# 02_-_BOOT-Select.net
KiCad netlist of a schematic drawn in Altium Designer
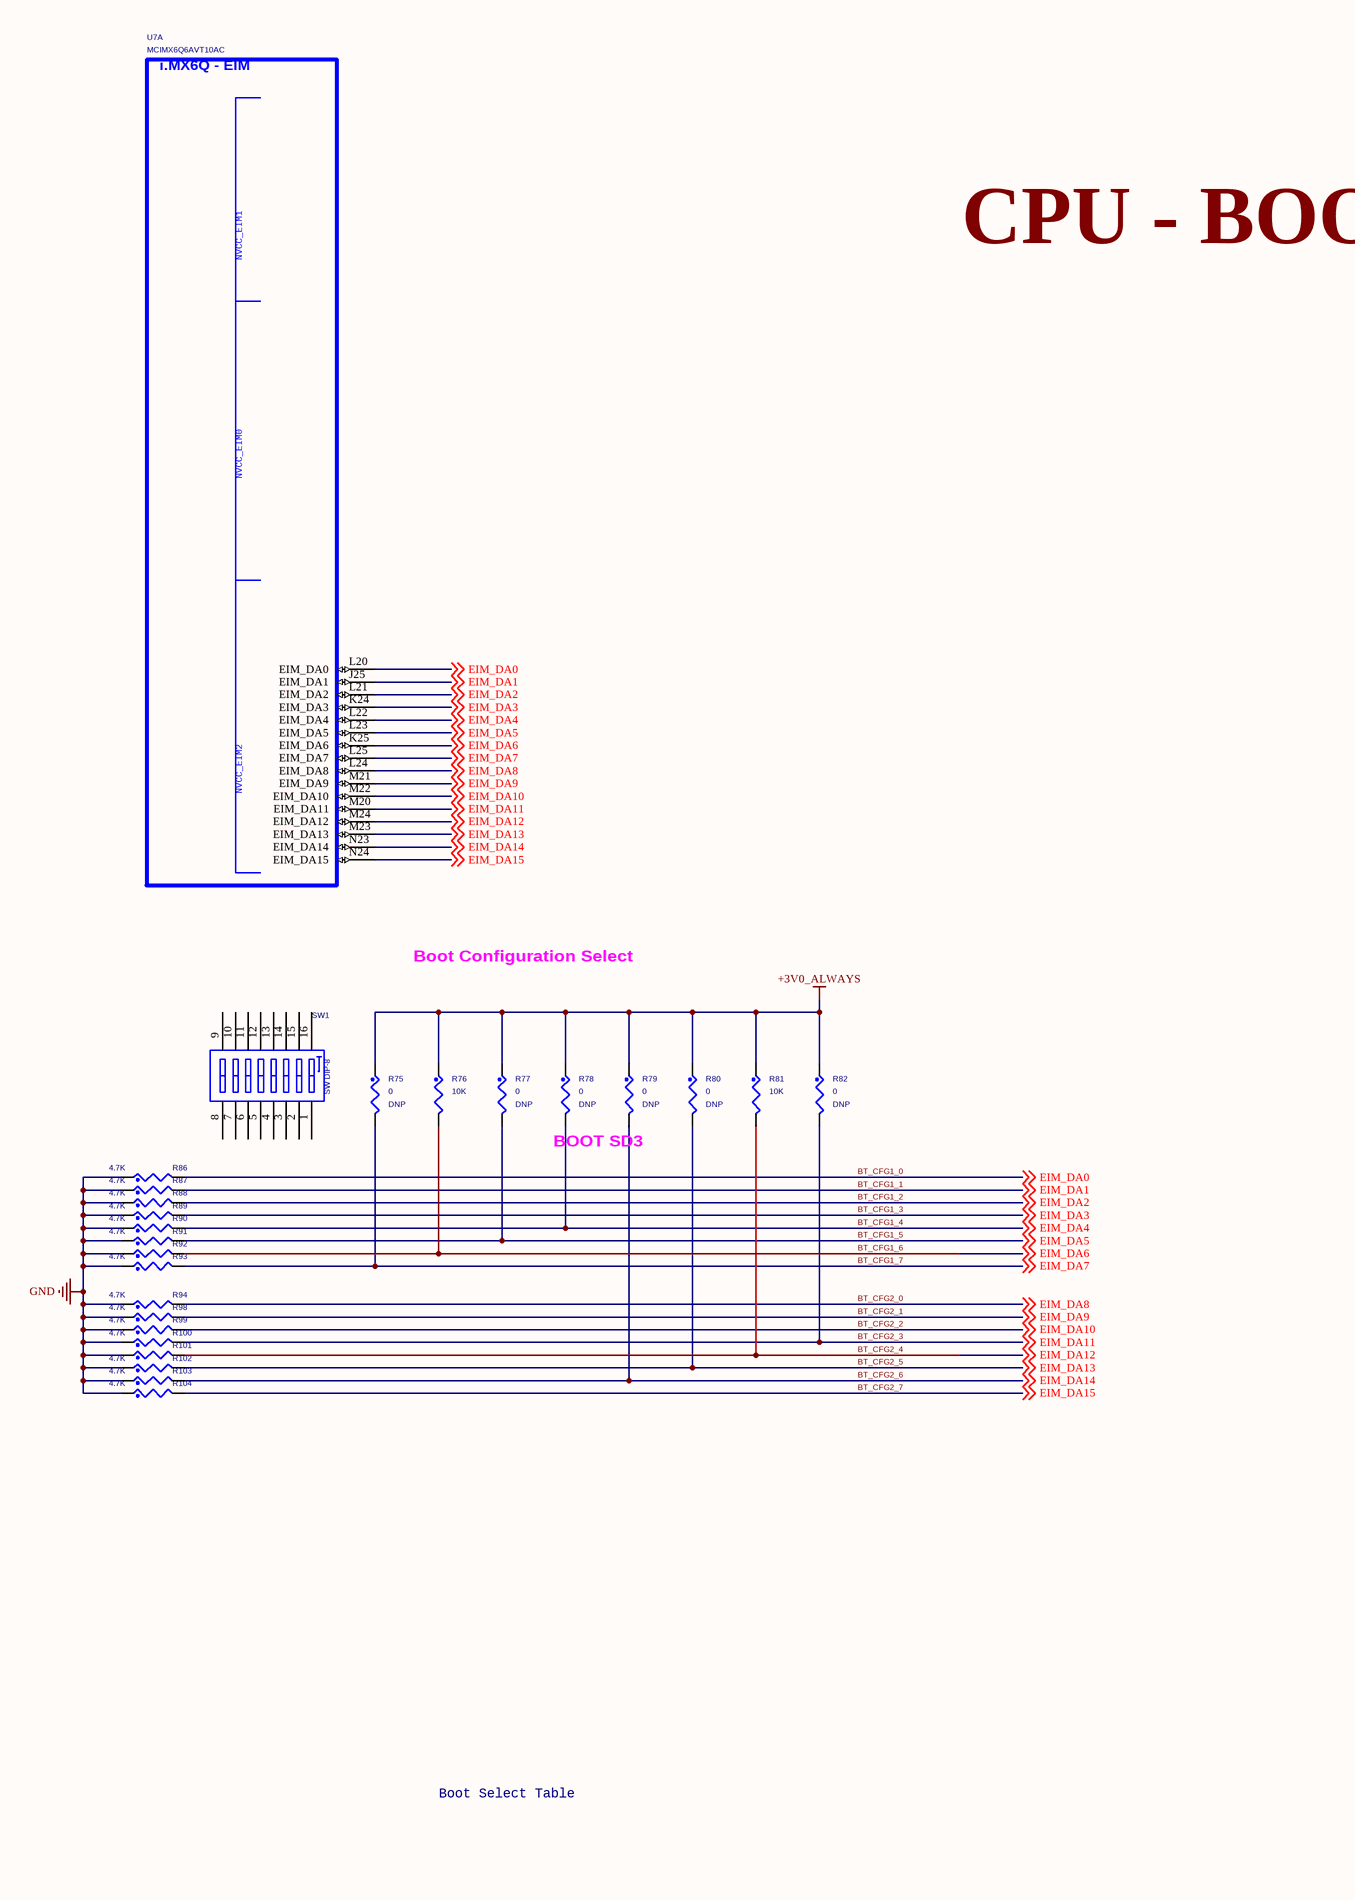
[diagram p0: [02] - BOOT-Select.SchDoc, left]
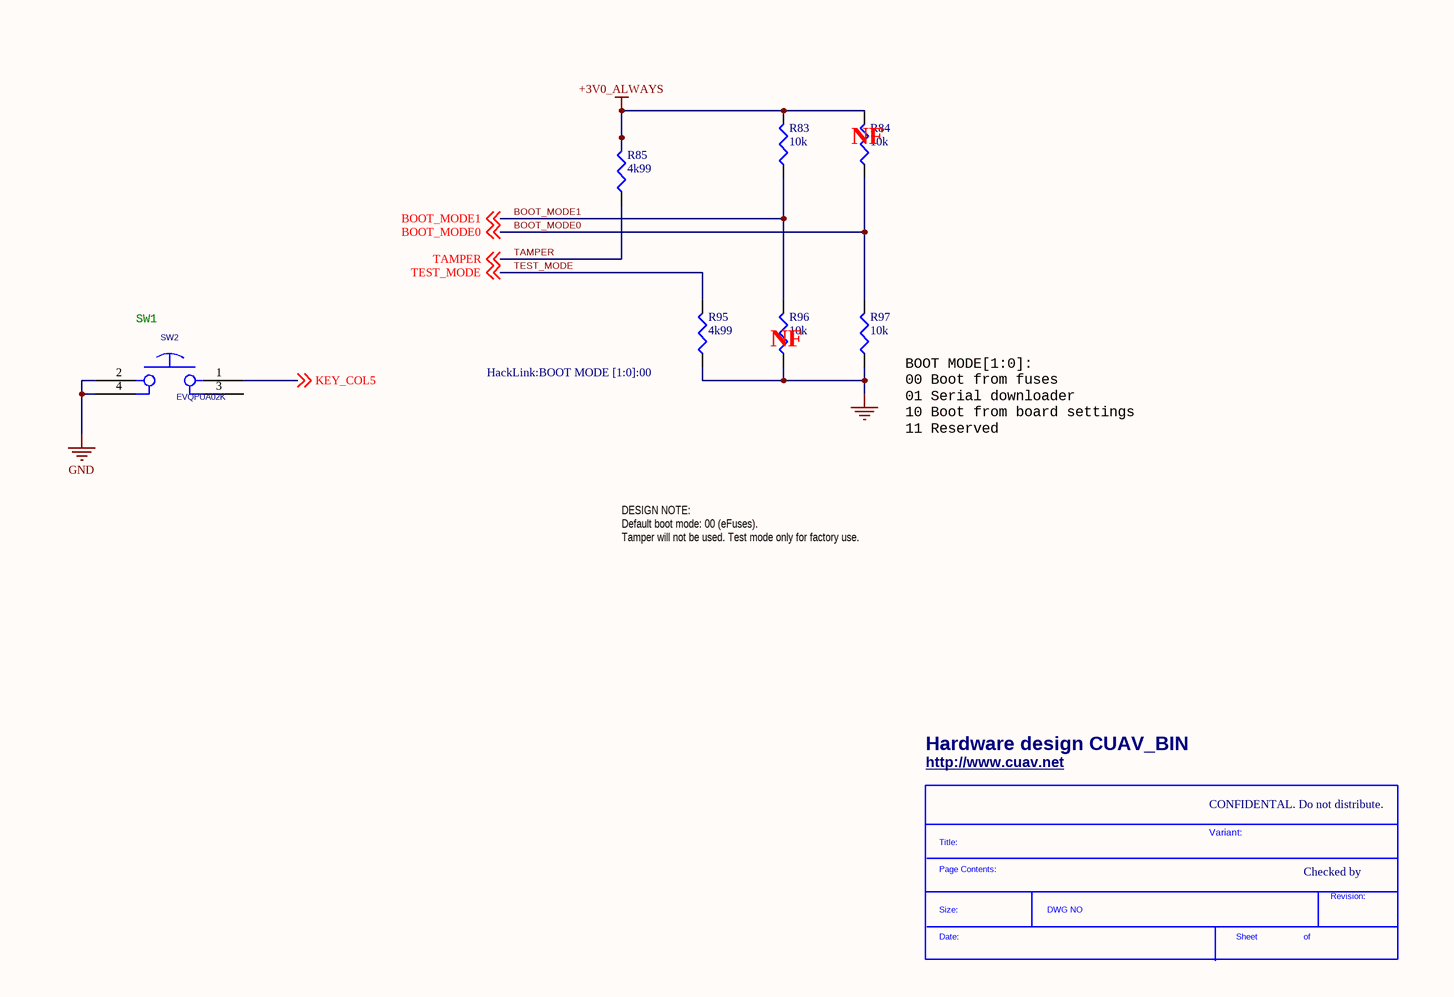
[diagram p1: [02] - BOOT-Select.SchDoc, right]

(export (version "E")
  (design (tool "Eeschema 10.0.6"))
  (components
    (comp (ref "*") (value "SDTitleBlock") (libsource (lib "*") (part "SDTitleBlock")))
    (comp (ref "R75")
      (value "0")
      (description "RES MF ZERO OHM 1/10W -- 0402")
      (fields (field (name "ASSY_OPT") "DNP"))
      (libsource (lib "*") (part "RES"))
    )
    (comp (ref "R76")
      (value "10K")
      (description "RES MF ZERO OHM 1/10W -- 0402")
      (libsource (lib "*") (part "RES"))
    )
    (comp (ref "R77")
      (value "0")
      (description "RES MF ZERO OHM 1/10W -- 0402")
      (fields (field (name "ASSY_OPT") "DNP"))
      (libsource (lib "*") (part "RES"))
    )
    (comp (ref "R78")
      (value "0")
      (description "RES MF ZERO OHM 1/10W -- 0402")
      (fields (field (name "ASSY_OPT") "DNP"))
      (libsource (lib "*") (part "RES"))
    )
    (comp (ref "R79")
      (value "0")
      (description "RES MF ZERO OHM 1/10W -- 0402")
      (fields (field (name "ASSY_OPT") "DNP"))
      (libsource (lib "*") (part "RES"))
    )
    (comp (ref "R80")
      (value "0")
      (description "RES MF ZERO OHM 1/10W -- 0402")
      (fields (field (name "ASSY_OPT") "DNP"))
      (libsource (lib "*") (part "RES"))
    )
    (comp (ref "R81")
      (value "10K")
      (description "RES MF ZERO OHM 1/10W -- 0402")
      (libsource (lib "*") (part "RES"))
    )
    (comp (ref "R82")
      (value "0")
      (description "RES MF ZERO OHM 1/10W -- 0402")
      (fields (field (name "ASSY_OPT") "DNP"))
      (libsource (lib "*") (part "RES"))
    )
    (comp (ref "R83")
      (value "10k")
      (footprint "R0402")
      (description "RES 10.0K OHM 1/16W 1% 0402 SMD")
      (fields
        (field (name "MANUFACTURER") "Yageo")
        (field (name "MANUFACTURER PART NUMBER") "RC0402FR-0710KL")
      )
      (libsource (lib "Integrated_Library_RF_FEB_2012") (part "RC0402FR-0710KL"))
    )
    (comp (ref "R84")
      (value "10k")
      (footprint "R0402")
      (description "RES 10.0K OHM 1/16W 1% 0402 SMD")
      (fields
        (field (name "MANUFACTURER") "Yageo")
        (field (name "MANUFACTURER PART NUMBER") "RC0402FR-0710KL")
      )
      (libsource (lib "Integrated_Library_RF_FEB_2012") (part "RC0402FR-0710KL"))
    )
    (comp (ref "R85")
      (value "4k99")
      (footprint "R0402")
      (description "RES TF 4.99K OHM 1% 1/16W 0402")
      (fields
        (field (name "MANUFACTURER") "Stackpole Electronics Inc")
        (field (name "MANUFACTURER PART NUMBER") "RMCF0402FT4K99")
      )
      (libsource (lib "Integrated_Library_RF_FEB_2012") (part "RMCF0402FT4K99"))
    )
    (comp (ref "R86")
      (value "4.7K")
      (description "RES MF 4.70K 1/16W 1% 0402")
      (fields (field (name "TOLERANCE") "1%"))
      (libsource (lib "*") (part "RES"))
    )
    (comp (ref "R87")
      (value "4.7K")
      (description "RES MF 4.70K 1/16W 1% 0402")
      (fields (field (name "TOLERANCE") "1%"))
      (libsource (lib "*") (part "RES"))
    )
    (comp (ref "R88")
      (value "4.7K")
      (description "RES MF 4.70K 1/16W 1% 0402")
      (fields (field (name "TOLERANCE") "1%"))
      (libsource (lib "*") (part "RES"))
    )
    (comp (ref "R89")
      (value "4.7K")
      (description "RES MF 4.70K 1/16W 1% 0402")
      (fields (field (name "TOLERANCE") "1%"))
      (libsource (lib "*") (part "RES"))
    )
    (comp (ref "R90")
      (value "4.7K")
      (description "RES MF 4.70K 1/16W 1% 0402")
      (fields (field (name "TOLERANCE") "1%"))
      (libsource (lib "*") (part "RES"))
    )
    (comp (ref "R91")
      (value "4.7K")
      (description "RES MF 4.70K 1/16W 1% 0402")
      (fields (field (name "TOLERANCE") "1%"))
      (libsource (lib "*") (part "RES"))
    )
    (comp (ref "R92")
      (value "~")
      (description "RES MF 4.70K 1/16W 1% 0402")
      (fields (field (name "TOLERANCE") "1%"))
      (libsource (lib "*") (part "RES"))
    )
    (comp (ref "R93")
      (value "4.7K")
      (description "RES MF 4.70K 1/16W 1% 0402")
      (fields (field (name "TOLERANCE") "1%"))
      (libsource (lib "*") (part "RES"))
    )
    (comp (ref "R94")
      (value "4.7K")
      (description "RES MF 4.70K 1/16W 1% 0402")
      (fields (field (name "TOLERANCE") "1%"))
      (libsource (lib "*") (part "RES"))
    )
    (comp (ref "R95")
      (value "4k99")
      (footprint "R0402")
      (description "RES TF 4.99K OHM 1% 1/16W 0402")
      (fields
        (field (name "MANUFACTURER") "Stackpole Electronics Inc")
        (field (name "MANUFACTURER PART NUMBER") "RMCF0402FT4K99")
      )
      (libsource (lib "Integrated_Library_RF_FEB_2012") (part "RMCF0402FT4K99"))
    )
    (comp (ref "R96")
      (value "10k")
      (footprint "R0402")
      (description "RES 10.0K OHM 1/16W 1% 0402 SMD")
      (fields
        (field (name "MANUFACTURER") "Yageo")
        (field (name "MANUFACTURER PART NUMBER") "RC0402FR-0710KL")
      )
      (libsource (lib "Integrated_Library_RF_FEB_2012") (part "RC0402FR-0710KL"))
    )
    (comp (ref "R97")
      (value "10k")
      (footprint "R0402")
      (description "RES 10.0K OHM 1/16W 1% 0402 SMD")
      (fields
        (field (name "MANUFACTURER") "Yageo")
        (field (name "MANUFACTURER PART NUMBER") "RC0402FR-0710KL")
      )
      (libsource (lib "Integrated_Library_RF_FEB_2012") (part "RC0402FR-0710KL"))
    )
    (comp (ref "R98")
      (value "4.7K")
      (description "RES MF 4.70K 1/16W 1% 0402")
      (fields (field (name "TOLERANCE") "1%"))
      (libsource (lib "*") (part "RES"))
    )
    (comp (ref "R99")
      (value "4.7K")
      (description "RES MF 4.70K 1/16W 1% 0402")
      (fields (field (name "TOLERANCE") "1%"))
      (libsource (lib "*") (part "RES"))
    )
    (comp (ref "R100")
      (value "4.7K")
      (description "RES MF 4.70K 1/16W 1% 0402")
      (fields (field (name "TOLERANCE") "1%"))
      (libsource (lib "*") (part "RES"))
    )
    (comp (ref "R101")
      (value "~")
      (description "RES MF 4.70K 1/16W 1% 0402")
      (fields (field (name "TOLERANCE") "1%"))
      (libsource (lib "*") (part "RES"))
    )
    (comp (ref "R102")
      (value "4.7K")
      (description "RES MF 4.70K 1/16W 1% 0402")
      (fields (field (name "TOLERANCE") "1%"))
      (libsource (lib "*") (part "RES"))
    )
    (comp (ref "R103")
      (value "4.7K")
      (description "RES MF 4.70K 1/16W 1% 0402")
      (fields (field (name "TOLERANCE") "1%"))
      (libsource (lib "*") (part "RES"))
    )
    (comp (ref "R104")
      (value "4.7K")
      (description "RES MF 4.70K 1/16W 1% 0402")
      (fields (field (name "TOLERANCE") "1%"))
      (libsource (lib "*") (part "RES"))
    )
    (comp (ref "SW1")
      (value "SW DIP-8")
      (description "SW SPST DIP 24V 16.67MA SMT")
      (libsource (lib "*") (part "SW_DIP_8"))
    )
    (comp (ref "SW2")
      (value "EVQPUA02K")
      (description "SW SPST NO PB 2.2N SIDE 12V 50MA SMT")
      (libsource (lib "*") (part "EDGE_MOUNT_PB_SW_2"))
    )
    (comp (ref "U7")
      (value "MCIMX6Q6AVT10AC")
      (description "IC MCU MX6QUAD ARM CORTEX-A9 FCPBGA624")
      (libsource (lib "*") (part "PCIMX6Q6VV1A"))
    )
  )
  (nets
    (net (code "1") (name "+3V0_ALWAYS") (class "Default")
      (node (ref "R75") (pin "1") (pinfunction "1_1") (pintype "passive"))
      (node (ref "R76") (pin "1") (pinfunction "1_1") (pintype "passive"))
      (node (ref "R77") (pin "1") (pinfunction "1_1") (pintype "passive"))
      (node (ref "R78") (pin "1") (pinfunction "1_1") (pintype "passive"))
      (node (ref "R79") (pin "1") (pinfunction "1_1") (pintype "passive"))
      (node (ref "R80") (pin "1") (pinfunction "1_1") (pintype "passive"))
      (node (ref "R81") (pin "1") (pinfunction "1_1") (pintype "passive"))
      (node (ref "R82") (pin "1") (pinfunction "1_1") (pintype "passive"))
      (node (ref "R83") (pin "2") (pinfunction "2_2") (pintype "passive"))
      (node (ref "R84") (pin "2") (pinfunction "2_2") (pintype "passive"))
      (node (ref "R85") (pin "2") (pinfunction "2_2") (pintype "passive"))
    )
    (net (code "2") (name "BOOT_MODE0") (class "Default")
      (node (ref "R84") (pin "1") (pinfunction "1_1") (pintype "passive"))
      (node (ref "R97") (pin "2") (pinfunction "2_2") (pintype "passive"))
    )
    (net (code "3") (name "BOOT_MODE1") (class "Default")
      (node (ref "R83") (pin "1") (pinfunction "1_1") (pintype "passive"))
      (node (ref "R96") (pin "2") (pinfunction "2_2") (pintype "passive"))
    )
    (net (code "4") (name "EIM_DA0") (class "Default")
      (node (ref "R86") (pin "2") (pinfunction "2_2") (pintype "passive"))
      (node (ref "U7") (pin "L20") (pinfunction "EIM_DA0_L20") (pintype "bidirectional"))
    )
    (net (code "5") (name "EIM_DA1") (class "Default")
      (node (ref "R87") (pin "2") (pinfunction "2_2") (pintype "passive"))
      (node (ref "U7") (pin "J25") (pinfunction "EIM_DA1_J25") (pintype "bidirectional"))
    )
    (net (code "6") (name "EIM_DA2") (class "Default")
      (node (ref "R88") (pin "2") (pinfunction "2_2") (pintype "passive"))
      (node (ref "U7") (pin "L21") (pinfunction "EIM_DA2_L21") (pintype "bidirectional"))
    )
    (net (code "7") (name "EIM_DA3") (class "Default")
      (node (ref "R89") (pin "2") (pinfunction "2_2") (pintype "passive"))
      (node (ref "U7") (pin "K24") (pinfunction "EIM_DA3_K24") (pintype "bidirectional"))
    )
    (net (code "8") (name "EIM_DA4") (class "Default")
      (node (ref "R78") (pin "2") (pinfunction "2_2") (pintype "passive"))
      (node (ref "R90") (pin "2") (pinfunction "2_2") (pintype "passive"))
      (node (ref "U7") (pin "L22") (pinfunction "EIM_DA4_L22") (pintype "bidirectional"))
    )
    (net (code "9") (name "EIM_DA5") (class "Default")
      (node (ref "R77") (pin "2") (pinfunction "2_2") (pintype "passive"))
      (node (ref "R91") (pin "2") (pinfunction "2_2") (pintype "passive"))
      (node (ref "U7") (pin "L23") (pinfunction "EIM_DA5_L23") (pintype "bidirectional"))
    )
    (net (code "10") (name "EIM_DA6") (class "Default")
      (node (ref "R76") (pin "2") (pinfunction "2_2") (pintype "passive"))
      (node (ref "R92") (pin "2") (pinfunction "2_2") (pintype "passive"))
      (node (ref "U7") (pin "K25") (pinfunction "EIM_DA6_K25") (pintype "bidirectional"))
    )
    (net (code "11") (name "EIM_DA7") (class "Default")
      (node (ref "R75") (pin "2") (pinfunction "2_2") (pintype "passive"))
      (node (ref "R93") (pin "2") (pinfunction "2_2") (pintype "passive"))
      (node (ref "U7") (pin "L25") (pinfunction "EIM_DA7_L25") (pintype "bidirectional"))
    )
    (net (code "12") (name "EIM_DA8") (class "Default")
      (node (ref "R94") (pin "2") (pinfunction "2_2") (pintype "passive"))
      (node (ref "U7") (pin "L24") (pinfunction "EIM_DA8_L24") (pintype "bidirectional"))
    )
    (net (code "13") (name "EIM_DA9") (class "Default")
      (node (ref "R98") (pin "2") (pinfunction "2_2") (pintype "passive"))
      (node (ref "U7") (pin "M21") (pinfunction "EIM_DA9_M21") (pintype "bidirectional"))
    )
    (net (code "14") (name "EIM_DA10") (class "Default")
      (node (ref "R99") (pin "2") (pinfunction "2_2") (pintype "passive"))
      (node (ref "U7") (pin "M22") (pinfunction "EIM_DA10_M22") (pintype "bidirectional"))
    )
    (net (code "15") (name "EIM_DA11") (class "Default")
      (node (ref "R100") (pin "2") (pinfunction "2_2") (pintype "passive"))
      (node (ref "R82") (pin "2") (pinfunction "2_2") (pintype "passive"))
      (node (ref "U7") (pin "M20") (pinfunction "EIM_DA11_M20") (pintype "bidirectional"))
    )
    (net (code "16") (name "EIM_DA12") (class "Default")
      (node (ref "R101") (pin "2") (pinfunction "2_2") (pintype "passive"))
      (node (ref "R81") (pin "2") (pinfunction "2_2") (pintype "passive"))
      (node (ref "U7") (pin "M24") (pinfunction "EIM_DA12_M24") (pintype "bidirectional"))
    )
    (net (code "17") (name "EIM_DA13") (class "Default")
      (node (ref "R102") (pin "2") (pinfunction "2_2") (pintype "passive"))
      (node (ref "R80") (pin "2") (pinfunction "2_2") (pintype "passive"))
      (node (ref "U7") (pin "M23") (pinfunction "EIM_DA13_M23") (pintype "bidirectional"))
    )
    (net (code "18") (name "EIM_DA14") (class "Default")
      (node (ref "R103") (pin "2") (pinfunction "2_2") (pintype "passive"))
      (node (ref "R79") (pin "2") (pinfunction "2_2") (pintype "passive"))
      (node (ref "U7") (pin "N23") (pinfunction "EIM_DA14_N23") (pintype "bidirectional"))
    )
    (net (code "19") (name "EIM_DA15") (class "Default")
      (node (ref "R104") (pin "2") (pinfunction "2_2") (pintype "passive"))
      (node (ref "U7") (pin "N24") (pinfunction "EIM_DA15_N24") (pintype "bidirectional"))
    )
    (net (code "20") (name "GND") (class "Default")
      (node (ref "R100") (pin "1") (pinfunction "1_1") (pintype "passive"))
      (node (ref "R101") (pin "1") (pinfunction "1_1") (pintype "passive"))
      (node (ref "R102") (pin "1") (pinfunction "1_1") (pintype "passive"))
      (node (ref "R103") (pin "1") (pinfunction "1_1") (pintype "passive"))
      (node (ref "R104") (pin "1") (pinfunction "1_1") (pintype "passive"))
      (node (ref "R86") (pin "1") (pinfunction "1_1") (pintype "passive"))
      (node (ref "R87") (pin "1") (pinfunction "1_1") (pintype "passive"))
      (node (ref "R88") (pin "1") (pinfunction "1_1") (pintype "passive"))
      (node (ref "R89") (pin "1") (pinfunction "1_1") (pintype "passive"))
      (node (ref "R90") (pin "1") (pinfunction "1_1") (pintype "passive"))
      (node (ref "R91") (pin "1") (pinfunction "1_1") (pintype "passive"))
      (node (ref "R92") (pin "1") (pinfunction "1_1") (pintype "passive"))
      (node (ref "R93") (pin "1") (pinfunction "1_1") (pintype "passive"))
      (node (ref "R94") (pin "1") (pinfunction "1_1") (pintype "passive"))
      (node (ref "R95") (pin "1") (pinfunction "1_1") (pintype "passive"))
      (node (ref "R96") (pin "1") (pinfunction "1_1") (pintype "passive"))
      (node (ref "R97") (pin "1") (pinfunction "1_1") (pintype "passive"))
      (node (ref "R98") (pin "1") (pinfunction "1_1") (pintype "passive"))
      (node (ref "R99") (pin "1") (pinfunction "1_1") (pintype "passive"))
      (node (ref "SW2") (pin "2") (pinfunction "2_2") (pintype "passive"))
      (node (ref "SW2") (pin "4") (pinfunction "4_4") (pintype "passive"))
    )
    (net (code "21") (name "KEY_COL5") (class "Default")
      (node (ref "SW2") (pin "1") (pinfunction "1_1") (pintype "passive"))
    )
    (net (code "22") (name "TAMPER") (class "Default")
      (node (ref "R85") (pin "1") (pinfunction "1_1") (pintype "passive"))
    )
    (net (code "23") (name "TEST_MODE") (class "Default")
      (node (ref "R95") (pin "2") (pinfunction "2_2") (pintype "passive"))
    )
    (net (code "24") (name "unconnected-(SW1-Pad1)") (class "Default")
      (node (ref "SW1") (pin "1") (pinfunction "1_1") (pintype "passive"))
    )
    (net (code "25") (name "unconnected-(SW1-Pad2)") (class "Default")
      (node (ref "SW1") (pin "2") (pinfunction "2_2") (pintype "passive"))
    )
    (net (code "26") (name "unconnected-(SW1-Pad3)") (class "Default")
      (node (ref "SW1") (pin "3") (pinfunction "3_3") (pintype "passive"))
    )
    (net (code "27") (name "unconnected-(SW1-Pad4)") (class "Default")
      (node (ref "SW1") (pin "4") (pinfunction "4_4") (pintype "passive"))
    )
    (net (code "28") (name "unconnected-(SW1-Pad5)") (class "Default")
      (node (ref "SW1") (pin "5") (pinfunction "5_5") (pintype "passive"))
    )
    (net (code "29") (name "unconnected-(SW1-Pad6)") (class "Default")
      (node (ref "SW1") (pin "6") (pinfunction "6_6") (pintype "passive"))
    )
    (net (code "30") (name "unconnected-(SW1-Pad7)") (class "Default")
      (node (ref "SW1") (pin "7") (pinfunction "7_7") (pintype "passive"))
    )
    (net (code "31") (name "unconnected-(SW1-Pad8)") (class "Default")
      (node (ref "SW1") (pin "8") (pinfunction "8_8") (pintype "passive"))
    )
    (net (code "32") (name "unconnected-(SW1-Pad9)") (class "Default")
      (node (ref "SW1") (pin "9") (pinfunction "9_9") (pintype "passive"))
    )
    (net (code "33") (name "unconnected-(SW1-Pad10)") (class "Default")
      (node (ref "SW1") (pin "10") (pinfunction "10_10") (pintype "passive"))
    )
    (net (code "34") (name "unconnected-(SW1-Pad11)") (class "Default")
      (node (ref "SW1") (pin "11") (pinfunction "11_11") (pintype "passive"))
    )
    (net (code "35") (name "unconnected-(SW1-Pad12)") (class "Default")
      (node (ref "SW1") (pin "12") (pinfunction "12_12") (pintype "passive"))
    )
    (net (code "36") (name "unconnected-(SW1-Pad13)") (class "Default")
      (node (ref "SW1") (pin "13") (pinfunction "13_13") (pintype "passive"))
    )
    (net (code "37") (name "unconnected-(SW1-Pad14)") (class "Default")
      (node (ref "SW1") (pin "14") (pinfunction "14_14") (pintype "passive"))
    )
    (net (code "38") (name "unconnected-(SW1-Pad15)") (class "Default")
      (node (ref "SW1") (pin "15") (pinfunction "15_15") (pintype "passive"))
    )
    (net (code "39") (name "unconnected-(SW1-Pad16)") (class "Default")
      (node (ref "SW1") (pin "16") (pinfunction "16_16") (pintype "passive"))
    )
    (net (code "40") (name "unconnected-(SW2-Pad3)") (class "Default")
      (node (ref "SW2") (pin "3") (pinfunction "3_3") (pintype "passive"))
    )
  )
)
